# untitled.net
KiCad netlist of a schematic drawn in EAGLE
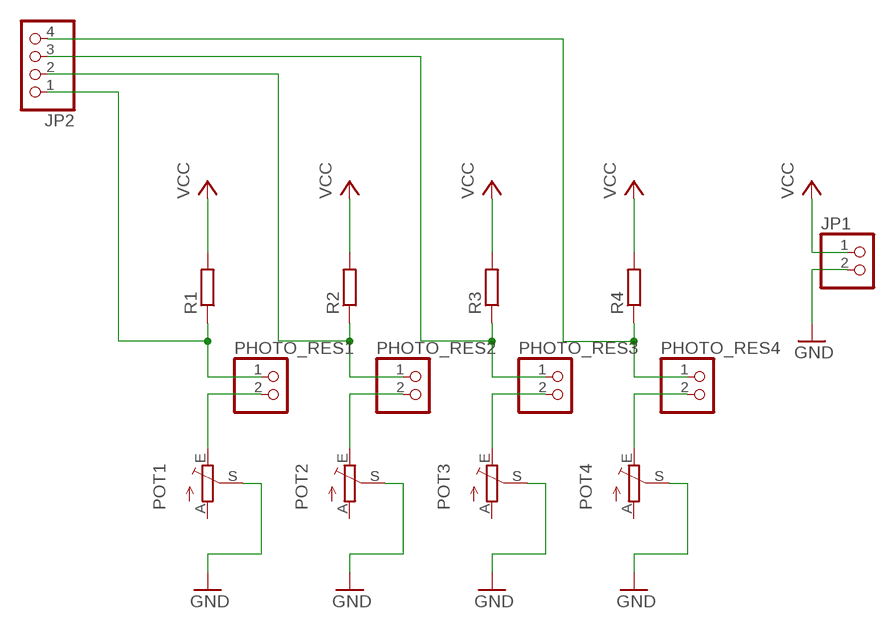
[diagram p0: schematic, sheet 1]

(export (version "E")
  (design (tool "Eeschema 10.0.6"))
  (components
    (comp (ref "JP1")
      (value "PINHD-1X2")
      (footprint "eagle-import:1X02")
      (libsource (lib "eagle-import") (part "PINHD-1X2"))
    )
    (comp (ref "JP2")
      (value "PINHD-1X4")
      (footprint "eagle-import:1X04")
      (libsource (lib "eagle-import") (part "PINHD-1X4"))
    )
    (comp (ref "PHOTO_RES1")
      (value "PINHD-1X2")
      (footprint "eagle-import:1X02")
      (libsource (lib "eagle-import") (part "PINHD-1X2"))
    )
    (comp (ref "PHOTO_RES2")
      (value "PINHD-1X2")
      (footprint "eagle-import:1X02")
      (libsource (lib "eagle-import") (part "PINHD-1X2"))
    )
    (comp (ref "PHOTO_RES3")
      (value "PINHD-1X2")
      (footprint "eagle-import:1X02")
      (libsource (lib "eagle-import") (part "PINHD-1X2"))
    )
    (comp (ref "PHOTO_RES4")
      (value "PINHD-1X2")
      (footprint "eagle-import:1X02")
      (libsource (lib "eagle-import") (part "PINHD-1X2"))
    )
    (comp (ref "POT1")
      (value "TRIM_EU-RJ9W")
      (footprint "eagle-import:RJ9W")
      (libsource (lib "eagle-import") (part "TRIM_EU-RJ9W"))
    )
    (comp (ref "POT2")
      (value "TRIM_EU-RJ9W")
      (footprint "eagle-import:RJ9W")
      (libsource (lib "eagle-import") (part "TRIM_EU-RJ9W"))
    )
    (comp (ref "POT3")
      (value "TRIM_EU-RJ9W")
      (footprint "eagle-import:RJ9W")
      (libsource (lib "eagle-import") (part "TRIM_EU-RJ9W"))
    )
    (comp (ref "POT4")
      (value "TRIM_EU-RJ9W")
      (footprint "eagle-import:RJ9W")
      (libsource (lib "eagle-import") (part "TRIM_EU-RJ9W"))
    )
    (comp (ref "R1")
      (value "R-EU_0207/7")
      (footprint "eagle-import:0207_7")
      (libsource (lib "eagle-import") (part "R-EU_0207/7"))
    )
    (comp (ref "R2")
      (value "R-EU_0207/7")
      (footprint "eagle-import:0207_7")
      (libsource (lib "eagle-import") (part "R-EU_0207/7"))
    )
    (comp (ref "R3")
      (value "R-EU_0207/7")
      (footprint "eagle-import:0207_7")
      (libsource (lib "eagle-import") (part "R-EU_0207/7"))
    )
    (comp (ref "R4")
      (value "R-EU_0207/7")
      (footprint "eagle-import:0207_7")
      (libsource (lib "eagle-import") (part "R-EU_0207/7"))
    )
  )
  (nets
    (net (code "1") (name "GND") (class "Default")
      (node (ref "JP1") (pin "2") (pinfunction "2_2") (pintype "passive"))
      (node (ref "POT1") (pin "S") (pinfunction "S_S") (pintype "passive"))
      (node (ref "POT2") (pin "S") (pinfunction "S_S") (pintype "passive"))
      (node (ref "POT3") (pin "S") (pinfunction "S_S") (pintype "passive"))
      (node (ref "POT4") (pin "S") (pinfunction "S_S") (pintype "passive"))
    )
    (net (code "2") (name "Net-(JP2-Pad1)") (class "Default")
      (node (ref "JP2") (pin "1") (pinfunction "1_1") (pintype "passive"))
      (node (ref "PHOTO_RES1") (pin "1") (pinfunction "1_1") (pintype "passive"))
      (node (ref "R1") (pin "1") (pinfunction "1_1") (pintype "passive"))
    )
    (net (code "3") (name "Net-(JP2-Pad2)") (class "Default")
      (node (ref "JP2") (pin "2") (pinfunction "2_2") (pintype "passive"))
      (node (ref "PHOTO_RES2") (pin "1") (pinfunction "1_1") (pintype "passive"))
      (node (ref "R2") (pin "1") (pinfunction "1_1") (pintype "passive"))
    )
    (net (code "4") (name "Net-(JP2-Pad3)") (class "Default")
      (node (ref "JP2") (pin "3") (pinfunction "3_3") (pintype "passive"))
      (node (ref "PHOTO_RES3") (pin "1") (pinfunction "1_1") (pintype "passive"))
      (node (ref "R3") (pin "1") (pinfunction "1_1") (pintype "passive"))
    )
    (net (code "5") (name "Net-(JP2-Pad4)") (class "Default")
      (node (ref "JP2") (pin "4") (pinfunction "4_4") (pintype "passive"))
      (node (ref "PHOTO_RES4") (pin "1") (pinfunction "1_1") (pintype "passive"))
      (node (ref "R4") (pin "1") (pinfunction "1_1") (pintype "passive"))
    )
    (net (code "6") (name "Net-(PHOTO_RES1-Pad2)") (class "Default")
      (node (ref "PHOTO_RES1") (pin "2") (pinfunction "2_2") (pintype "passive"))
      (node (ref "POT1") (pin "E") (pinfunction "E_E") (pintype "passive"))
    )
    (net (code "7") (name "Net-(PHOTO_RES2-Pad2)") (class "Default")
      (node (ref "PHOTO_RES2") (pin "2") (pinfunction "2_2") (pintype "passive"))
      (node (ref "POT2") (pin "E") (pinfunction "E_E") (pintype "passive"))
    )
    (net (code "8") (name "Net-(PHOTO_RES3-Pad2)") (class "Default")
      (node (ref "PHOTO_RES3") (pin "2") (pinfunction "2_2") (pintype "passive"))
      (node (ref "POT3") (pin "E") (pinfunction "E_E") (pintype "passive"))
    )
    (net (code "9") (name "Net-(PHOTO_RES4-Pad2)") (class "Default")
      (node (ref "PHOTO_RES4") (pin "2") (pinfunction "2_2") (pintype "passive"))
      (node (ref "POT4") (pin "E") (pinfunction "E_E") (pintype "passive"))
    )
    (net (code "10") (name "VCC") (class "Default")
      (node (ref "JP1") (pin "1") (pinfunction "1_1") (pintype "passive"))
      (node (ref "R1") (pin "2") (pinfunction "2_2") (pintype "passive"))
      (node (ref "R2") (pin "2") (pinfunction "2_2") (pintype "passive"))
      (node (ref "R3") (pin "2") (pinfunction "2_2") (pintype "passive"))
      (node (ref "R4") (pin "2") (pinfunction "2_2") (pintype "passive"))
    )
    (net (code "11") (name "unconnected-(POT1-PadA)") (class "Default")
      (node (ref "POT1") (pin "A") (pinfunction "A_A") (pintype "passive"))
    )
    (net (code "12") (name "unconnected-(POT2-PadA)") (class "Default")
      (node (ref "POT2") (pin "A") (pinfunction "A_A") (pintype "passive"))
    )
    (net (code "13") (name "unconnected-(POT3-PadA)") (class "Default")
      (node (ref "POT3") (pin "A") (pinfunction "A_A") (pintype "passive"))
    )
    (net (code "14") (name "unconnected-(POT4-PadA)") (class "Default")
      (node (ref "POT4") (pin "A") (pinfunction "A_A") (pintype "passive"))
    )
  )
)
